# Esquematico.net
KiCad netlist of a schematic drawn in EAGLE
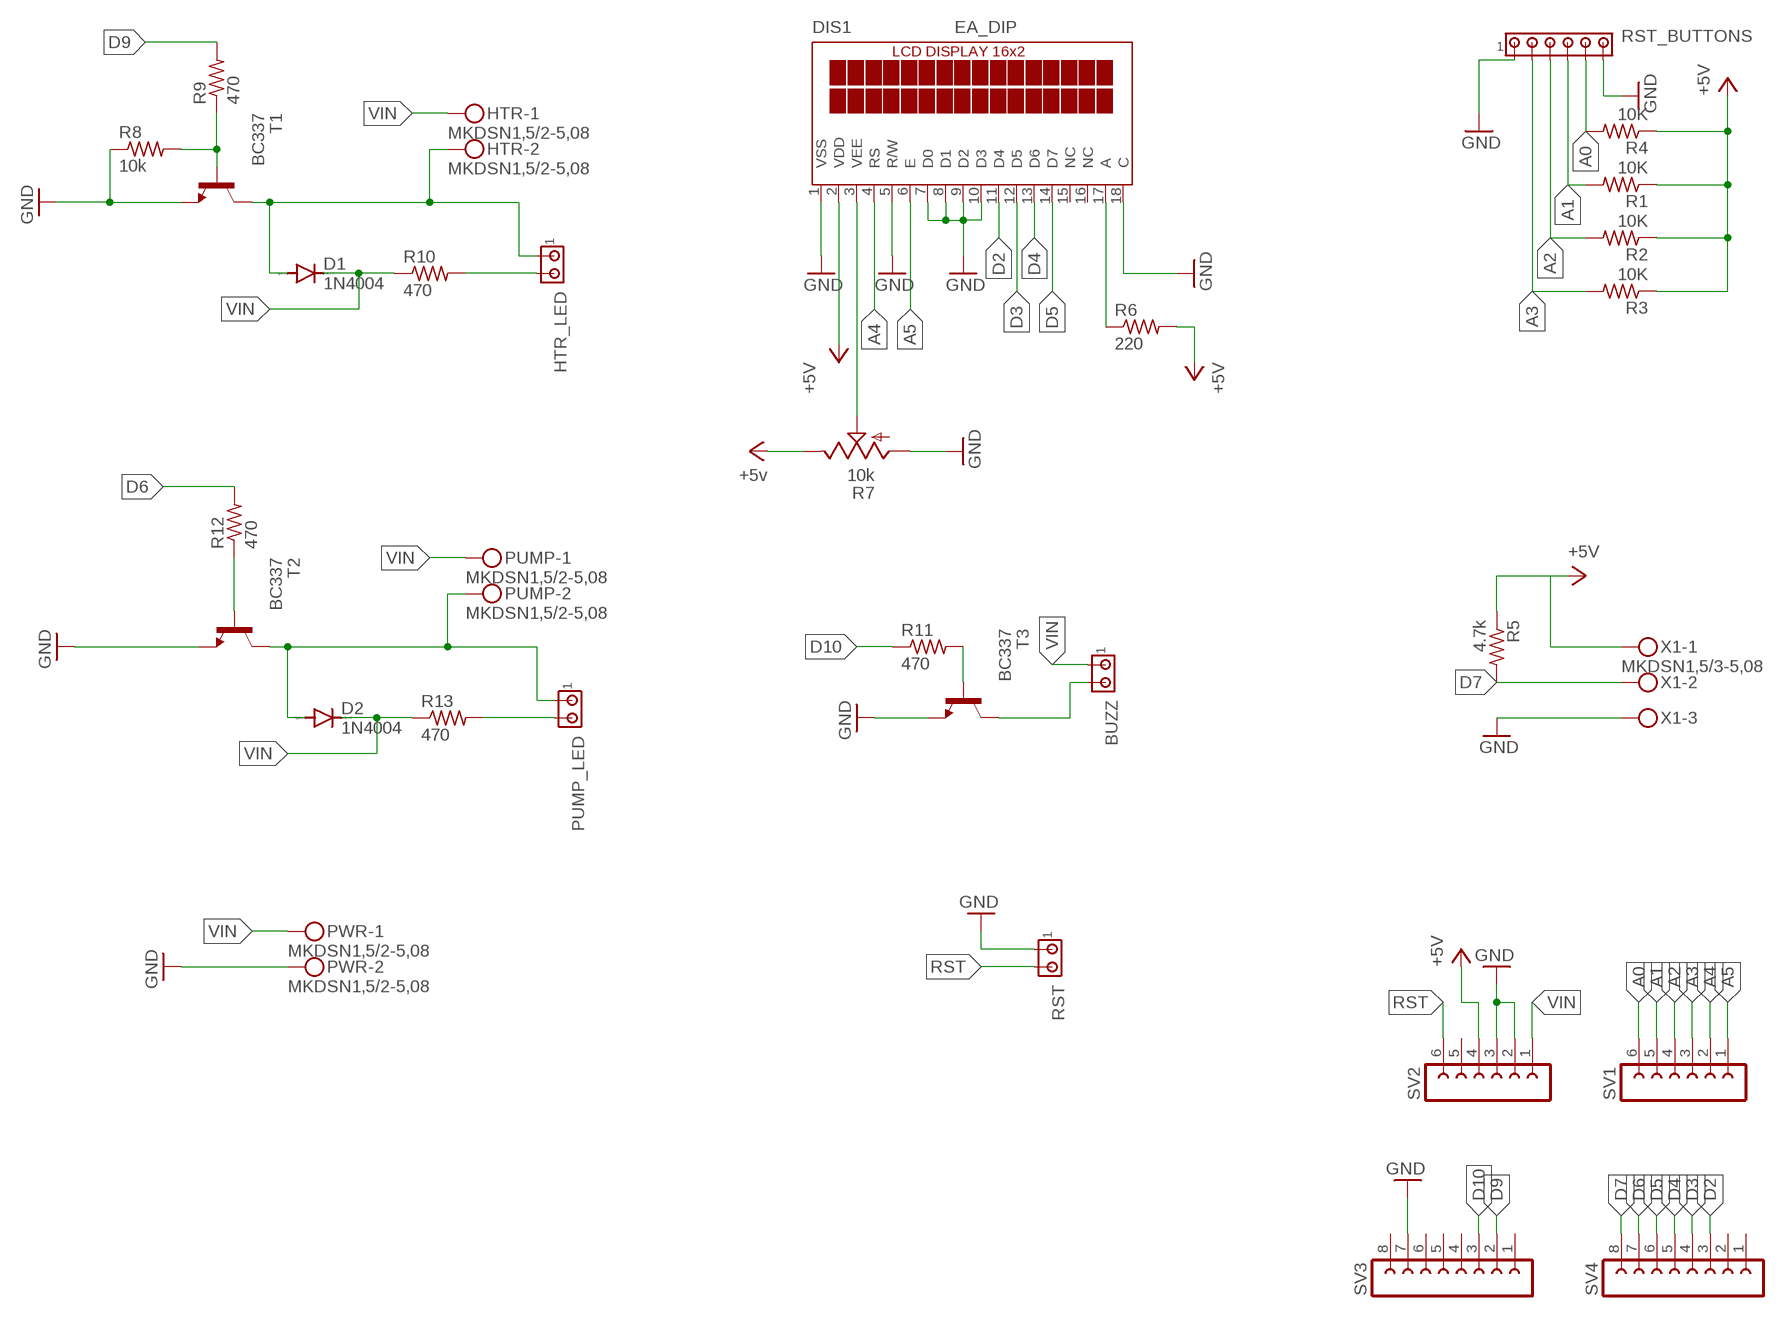
[diagram p0: schematic, sheet 1]

(export (version "E")
  (design (tool "Eeschema 10.0.6"))
  (components
    (comp (ref "BUZZ")
      (value "MTA02-100")
      (footprint "eagle-import:10X02MTA")
      (libsource (lib "eagle-import") (part "MTA02-100"))
    )
    (comp (ref "D1")
      (value "1N4004")
      (footprint "eagle-import:DO41-10")
      (libsource (lib "eagle-import") (part "1N4004"))
    )
    (comp (ref "D2")
      (value "1N4004")
      (footprint "eagle-import:DO41-10")
      (libsource (lib "eagle-import") (part "1N4004"))
    )
    (comp (ref "DIS1")
      (value "EA_DIP")
      (footprint "eagle-import:EA_DIP")
      (libsource (lib "eagle-import") (part "EA_DIP"))
    )
    (comp (ref "HTR")
      (value "MKDSN1,5/2-5,08")
      (footprint "eagle-import:MKDSN1,5_2-5,08")
      (libsource (lib "eagle-import") (part "MKDSN1,5/2-5,08"))
    )
    (comp (ref "HTR_LED")
      (value "MTA02-100")
      (footprint "eagle-import:10X02MTA")
      (libsource (lib "eagle-import") (part "MTA02-100"))
    )
    (comp (ref "PUMP")
      (value "MKDSN1,5/2-5,08")
      (footprint "eagle-import:MKDSN1,5_2-5,08")
      (libsource (lib "eagle-import") (part "MKDSN1,5/2-5,08"))
    )
    (comp (ref "PUMP_LED")
      (value "MTA02-100")
      (footprint "eagle-import:10X02MTA")
      (libsource (lib "eagle-import") (part "MTA02-100"))
    )
    (comp (ref "PWR")
      (value "MKDSN1,5/2-5,08")
      (footprint "eagle-import:MKDSN1,5_2-5,08")
      (libsource (lib "eagle-import") (part "MKDSN1,5/2-5,08"))
    )
    (comp (ref "R1")
      (value "10K")
      (footprint "eagle-import:0204_5")
      (libsource (lib "eagle-import") (part "R-US_0204/5"))
    )
    (comp (ref "R2")
      (value "10K")
      (footprint "eagle-import:0204_5")
      (libsource (lib "eagle-import") (part "R-US_0204/5"))
    )
    (comp (ref "R3")
      (value "10K")
      (footprint "eagle-import:0204_5")
      (libsource (lib "eagle-import") (part "R-US_0204/5"))
    )
    (comp (ref "R4")
      (value "10K")
      (footprint "eagle-import:0204_5")
      (libsource (lib "eagle-import") (part "R-US_0204/5"))
    )
    (comp (ref "R5")
      (value "4.7k")
      (footprint "eagle-import:0204_5")
      (libsource (lib "eagle-import") (part "R-US_0204/5"))
    )
    (comp (ref "R6")
      (value "220")
      (footprint "eagle-import:0204_5")
      (libsource (lib "eagle-import") (part "R-US_0204/5"))
    )
    (comp (ref "R7")
      (value "10k")
      (footprint "eagle-import:B25P")
      (libsource (lib "eagle-import") (part "TRIM_US-B25P"))
    )
    (comp (ref "R8")
      (value "10k")
      (footprint "eagle-import:0204_5")
      (libsource (lib "eagle-import") (part "R-US_0204/5"))
    )
    (comp (ref "R9")
      (value "470")
      (footprint "eagle-import:0204_5")
      (libsource (lib "eagle-import") (part "R-US_0204/5"))
    )
    (comp (ref "R10")
      (value "470")
      (footprint "eagle-import:0204_5")
      (libsource (lib "eagle-import") (part "R-US_0204/5"))
    )
    (comp (ref "R11")
      (value "470")
      (footprint "eagle-import:0204_5")
      (libsource (lib "eagle-import") (part "R-US_0204/5"))
    )
    (comp (ref "R12")
      (value "470")
      (footprint "eagle-import:0204_5")
      (libsource (lib "eagle-import") (part "R-US_0204/5"))
    )
    (comp (ref "R13")
      (value "470")
      (footprint "eagle-import:0204_5")
      (libsource (lib "eagle-import") (part "R-US_0204/5"))
    )
    (comp (ref "RST")
      (value "MTA02-100")
      (footprint "eagle-import:10X02MTA")
      (libsource (lib "eagle-import") (part "MTA02-100"))
    )
    (comp (ref "RST_BUTTONS")
      (value "MTA06-100")
      (footprint "eagle-import:10X06MTA")
      (libsource (lib "eagle-import") (part "MTA06-100"))
    )
    (comp (ref "SV1")
      (value "FE06-1")
      (footprint "eagle-import:FE06")
      (libsource (lib "eagle-import") (part "FE06-1"))
    )
    (comp (ref "SV2")
      (value "FE06-1")
      (footprint "eagle-import:FE06")
      (libsource (lib "eagle-import") (part "FE06-1"))
    )
    (comp (ref "SV3")
      (value "FE08-1")
      (footprint "eagle-import:FE08")
      (libsource (lib "eagle-import") (part "FE08-1"))
    )
    (comp (ref "SV4")
      (value "FE08-1")
      (footprint "eagle-import:FE08")
      (libsource (lib "eagle-import") (part "FE08-1"))
    )
    (comp (ref "T1")
      (value "BC337")
      (footprint "eagle-import:TO92")
      (libsource (lib "eagle-import") (part "BC337"))
    )
    (comp (ref "T2")
      (value "BC337")
      (footprint "eagle-import:TO92")
      (libsource (lib "eagle-import") (part "BC337"))
    )
    (comp (ref "T3")
      (value "BC337")
      (footprint "eagle-import:TO92")
      (libsource (lib "eagle-import") (part "BC337"))
    )
    (comp (ref "X1")
      (value "MKDSN1,5/3-5,08")
      (footprint "eagle-import:MKDSN1,5_3-5,08")
      (libsource (lib "eagle-import") (part "MKDSN1,5/3-5,08"))
    )
  )
  (nets
    (net (code "1") (name "+5V") (class "Default")
      (node (ref "DIS1") (pin "2") (pinfunction "VDD_2") (pintype "power_in"))
      (node (ref "R1") (pin "1") (pinfunction "1_1") (pintype "passive"))
      (node (ref "R2") (pin "1") (pinfunction "1_1") (pintype "passive"))
      (node (ref "R3") (pin "1") (pinfunction "1_1") (pintype "passive"))
      (node (ref "R4") (pin "1") (pinfunction "1_1") (pintype "passive"))
      (node (ref "R5") (pin "1") (pinfunction "1_1") (pintype "passive"))
      (node (ref "R6") (pin "2") (pinfunction "2_2") (pintype "passive"))
      (node (ref "R7") (pin "E") (pinfunction "E_E") (pintype "passive"))
      (node (ref "SV2") (pin "4") (pinfunction "4_4") (pintype "passive"))
      (node (ref "X1") (pin "1") (pinfunction "KL_1") (pintype "passive"))
    )
    (net (code "2") (name "A0") (class "Default")
      (node (ref "R4") (pin "2") (pinfunction "2_2") (pintype "passive"))
      (node (ref "RST_BUTTONS") (pin "5") (pinfunction "5_5") (pintype "passive"))
      (node (ref "SV1") (pin "6") (pinfunction "6_6") (pintype "passive"))
    )
    (net (code "3") (name "A1") (class "Default")
      (node (ref "R1") (pin "2") (pinfunction "2_2") (pintype "passive"))
      (node (ref "RST_BUTTONS") (pin "4") (pinfunction "4_4") (pintype "passive"))
      (node (ref "SV1") (pin "5") (pinfunction "5_5") (pintype "passive"))
    )
    (net (code "4") (name "A2") (class "Default")
      (node (ref "R2") (pin "2") (pinfunction "2_2") (pintype "passive"))
      (node (ref "RST_BUTTONS") (pin "3") (pinfunction "3_3") (pintype "passive"))
      (node (ref "SV1") (pin "4") (pinfunction "4_4") (pintype "passive"))
    )
    (net (code "5") (name "A3") (class "Default")
      (node (ref "R3") (pin "2") (pinfunction "2_2") (pintype "passive"))
      (node (ref "RST_BUTTONS") (pin "2") (pinfunction "2_2") (pintype "passive"))
      (node (ref "SV1") (pin "3") (pinfunction "3_3") (pintype "passive"))
    )
    (net (code "6") (name "A4") (class "Default")
      (node (ref "DIS1") (pin "4") (pinfunction "RS_4") (pintype "input"))
      (node (ref "SV1") (pin "2") (pinfunction "2_2") (pintype "passive"))
    )
    (net (code "7") (name "A5") (class "Default")
      (node (ref "DIS1") (pin "6") (pinfunction "E_6") (pintype "input"))
      (node (ref "SV1") (pin "1") (pinfunction "1_1") (pintype "passive"))
    )
    (net (code "8") (name "D2") (class "Default")
      (node (ref "DIS1") (pin "11") (pinfunction "D4_11") (pintype "input"))
      (node (ref "SV4") (pin "3") (pinfunction "3_3") (pintype "passive"))
    )
    (net (code "9") (name "D3") (class "Default")
      (node (ref "DIS1") (pin "12") (pinfunction "D5_12") (pintype "input"))
      (node (ref "SV4") (pin "4") (pinfunction "4_4") (pintype "passive"))
    )
    (net (code "10") (name "D4") (class "Default")
      (node (ref "DIS1") (pin "13") (pinfunction "D6_13") (pintype "input"))
      (node (ref "SV4") (pin "5") (pinfunction "5_5") (pintype "passive"))
    )
    (net (code "11") (name "D5") (class "Default")
      (node (ref "DIS1") (pin "14") (pinfunction "D7_14") (pintype "input"))
      (node (ref "SV4") (pin "6") (pinfunction "6_6") (pintype "passive"))
    )
    (net (code "12") (name "D6") (class "Default")
      (node (ref "R12") (pin "2") (pinfunction "2_2") (pintype "passive"))
      (node (ref "SV4") (pin "7") (pinfunction "7_7") (pintype "passive"))
    )
    (net (code "13") (name "D7") (class "Default")
      (node (ref "R5") (pin "2") (pinfunction "2_2") (pintype "passive"))
      (node (ref "SV4") (pin "8") (pinfunction "8_8") (pintype "passive"))
      (node (ref "X1") (pin "2") (pinfunction "KL_2") (pintype "passive"))
    )
    (net (code "14") (name "D9") (class "Default")
      (node (ref "R9") (pin "2") (pinfunction "2_2") (pintype "passive"))
      (node (ref "SV3") (pin "2") (pinfunction "2_2") (pintype "passive"))
    )
    (net (code "15") (name "D10") (class "Default")
      (node (ref "R11") (pin "1") (pinfunction "1_1") (pintype "passive"))
      (node (ref "SV3") (pin "3") (pinfunction "3_3") (pintype "passive"))
    )
    (net (code "16") (name "GND") (class "Default")
      (node (ref "DIS1") (pin "1") (pinfunction "VSS_1") (pintype "power_in"))
      (node (ref "DIS1") (pin "10") (pinfunction "D3_10") (pintype "input"))
      (node (ref "DIS1") (pin "18") (pinfunction "C_18") (pintype "passive"))
      (node (ref "DIS1") (pin "5") (pinfunction "R/W_5") (pintype "input"))
      (node (ref "DIS1") (pin "7") (pinfunction "D0_7") (pintype "input"))
      (node (ref "DIS1") (pin "8") (pinfunction "D1_8") (pintype "input"))
      (node (ref "DIS1") (pin "9") (pinfunction "D2_9") (pintype "input"))
      (node (ref "PWR") (pin "2") (pinfunction "KL_2") (pintype "passive"))
      (node (ref "R7") (pin "A") (pinfunction "A_A") (pintype "passive"))
      (node (ref "R8") (pin "1") (pinfunction "1_1") (pintype "passive"))
      (node (ref "RST") (pin "1") (pinfunction "1_1") (pintype "passive"))
      (node (ref "RST_BUTTONS") (pin "1") (pinfunction "1_1") (pintype "passive"))
      (node (ref "RST_BUTTONS") (pin "6") (pinfunction "6_6") (pintype "passive"))
      (node (ref "SV2") (pin "2") (pinfunction "2_2") (pintype "passive"))
      (node (ref "SV2") (pin "3") (pinfunction "3_3") (pintype "passive"))
      (node (ref "SV3") (pin "7") (pinfunction "7_7") (pintype "passive"))
      (node (ref "T1") (pin "1") (pinfunction "E_1") (pintype "passive"))
      (node (ref "T2") (pin "1") (pinfunction "E_1") (pintype "passive"))
      (node (ref "T3") (pin "1") (pinfunction "E_1") (pintype "passive"))
      (node (ref "X1") (pin "3") (pinfunction "KL_3") (pintype "passive"))
    )
    (net (code "17") (name "Net-(DIS1-A)") (class "Default")
      (node (ref "DIS1") (pin "17") (pinfunction "A_17") (pintype "passive"))
      (node (ref "R6") (pin "1") (pinfunction "1_1") (pintype "passive"))
    )
    (net (code "18") (name "Net-(DIS1-VEE)") (class "Default")
      (node (ref "DIS1") (pin "3") (pinfunction "VEE_3") (pintype "power_in"))
      (node (ref "R7") (pin "S") (pinfunction "S_S") (pintype "passive"))
    )
    (net (code "19") (name "Net-(HTRB-KL)") (class "Default")
      (node (ref "D1") (pin "A") (pinfunction "A_A") (pintype "passive"))
      (node (ref "HTR") (pin "2") (pinfunction "KL_2") (pintype "passive"))
      (node (ref "HTR_LED") (pin "1") (pinfunction "1_1") (pintype "passive"))
      (node (ref "T1") (pin "3") (pinfunction "C_3") (pintype "passive"))
    )
    (net (code "20") (name "Net-(HTR_LED-Pad2)") (class "Default")
      (node (ref "HTR_LED") (pin "2") (pinfunction "2_2") (pintype "passive"))
      (node (ref "R10") (pin "2") (pinfunction "2_2") (pintype "passive"))
    )
    (net (code "21") (name "Net-(PUMPB-KL)") (class "Default")
      (node (ref "D2") (pin "A") (pinfunction "A_A") (pintype "passive"))
      (node (ref "PUMP") (pin "2") (pinfunction "KL_2") (pintype "passive"))
      (node (ref "PUMP_LED") (pin "1") (pinfunction "1_1") (pintype "passive"))
      (node (ref "T2") (pin "3") (pinfunction "C_3") (pintype "passive"))
    )
    (net (code "22") (name "Net-(PUMP_LED-Pad2)") (class "Default")
      (node (ref "PUMP_LED") (pin "2") (pinfunction "2_2") (pintype "passive"))
      (node (ref "R13") (pin "2") (pinfunction "2_2") (pintype "passive"))
    )
    (net (code "23") (name "Net-(T1-B)") (class "Default")
      (node (ref "R8") (pin "2") (pinfunction "2_2") (pintype "passive"))
      (node (ref "R9") (pin "1") (pinfunction "1_1") (pintype "passive"))
      (node (ref "T1") (pin "2") (pinfunction "B_2") (pintype "passive"))
    )
    (net (code "24") (name "Net-(T2-B)") (class "Default")
      (node (ref "R12") (pin "1") (pinfunction "1_1") (pintype "passive"))
      (node (ref "T2") (pin "2") (pinfunction "B_2") (pintype "passive"))
    )
    (net (code "25") (name "Net-(T3-B)") (class "Default")
      (node (ref "R11") (pin "2") (pinfunction "2_2") (pintype "passive"))
      (node (ref "T3") (pin "2") (pinfunction "B_2") (pintype "passive"))
    )
    (net (code "26") (name "Net-(T3-C)") (class "Default")
      (node (ref "BUZZ") (pin "2") (pinfunction "2_2") (pintype "passive"))
      (node (ref "T3") (pin "3") (pinfunction "C_3") (pintype "passive"))
    )
    (net (code "27") (name "RST") (class "Default")
      (node (ref "RST") (pin "2") (pinfunction "2_2") (pintype "passive"))
      (node (ref "SV2") (pin "6") (pinfunction "6_6") (pintype "passive"))
    )
    (net (code "28") (name "VIN") (class "Default")
      (node (ref "BUZZ") (pin "1") (pinfunction "1_1") (pintype "passive"))
      (node (ref "D1") (pin "C") (pinfunction "C_C") (pintype "passive"))
      (node (ref "D2") (pin "C") (pinfunction "C_C") (pintype "passive"))
      (node (ref "HTR") (pin "1") (pinfunction "KL_1") (pintype "passive"))
      (node (ref "PUMP") (pin "1") (pinfunction "KL_1") (pintype "passive"))
      (node (ref "PWR") (pin "1") (pinfunction "KL_1") (pintype "passive"))
      (node (ref "R10") (pin "1") (pinfunction "1_1") (pintype "passive"))
      (node (ref "R13") (pin "1") (pinfunction "1_1") (pintype "passive"))
      (node (ref "SV2") (pin "1") (pinfunction "1_1") (pintype "passive"))
    )
    (net (code "29") (name "unconnected-(DIS1-NC-Pad15)") (class "Default")
      (node (ref "DIS1") (pin "15") (pinfunction "NC_15") (pintype "no_connect"))
    )
    (net (code "30") (name "unconnected-(DIS1-NC-Pad16)") (class "Default")
      (node (ref "DIS1") (pin "16") (pinfunction "NC_16") (pintype "no_connect"))
    )
    (net (code "31") (name "unconnected-(SV2-Pad5)") (class "Default")
      (node (ref "SV2") (pin "5") (pinfunction "5_5") (pintype "passive"))
    )
    (net (code "32") (name "unconnected-(SV3-Pad1)") (class "Default")
      (node (ref "SV3") (pin "1") (pinfunction "1_1") (pintype "passive"))
    )
    (net (code "33") (name "unconnected-(SV3-Pad4)") (class "Default")
      (node (ref "SV3") (pin "4") (pinfunction "4_4") (pintype "passive"))
    )
    (net (code "34") (name "unconnected-(SV3-Pad5)") (class "Default")
      (node (ref "SV3") (pin "5") (pinfunction "5_5") (pintype "passive"))
    )
    (net (code "35") (name "unconnected-(SV3-Pad6)") (class "Default")
      (node (ref "SV3") (pin "6") (pinfunction "6_6") (pintype "passive"))
    )
    (net (code "36") (name "unconnected-(SV3-Pad8)") (class "Default")
      (node (ref "SV3") (pin "8") (pinfunction "8_8") (pintype "passive"))
    )
    (net (code "37") (name "unconnected-(SV4-Pad1)") (class "Default")
      (node (ref "SV4") (pin "1") (pinfunction "1_1") (pintype "passive"))
    )
    (net (code "38") (name "unconnected-(SV4-Pad2)") (class "Default")
      (node (ref "SV4") (pin "2") (pinfunction "2_2") (pintype "passive"))
    )
  )
)
